# SMT_sheet.net
KiCad netlist of a schematic drawn in Altium Designer
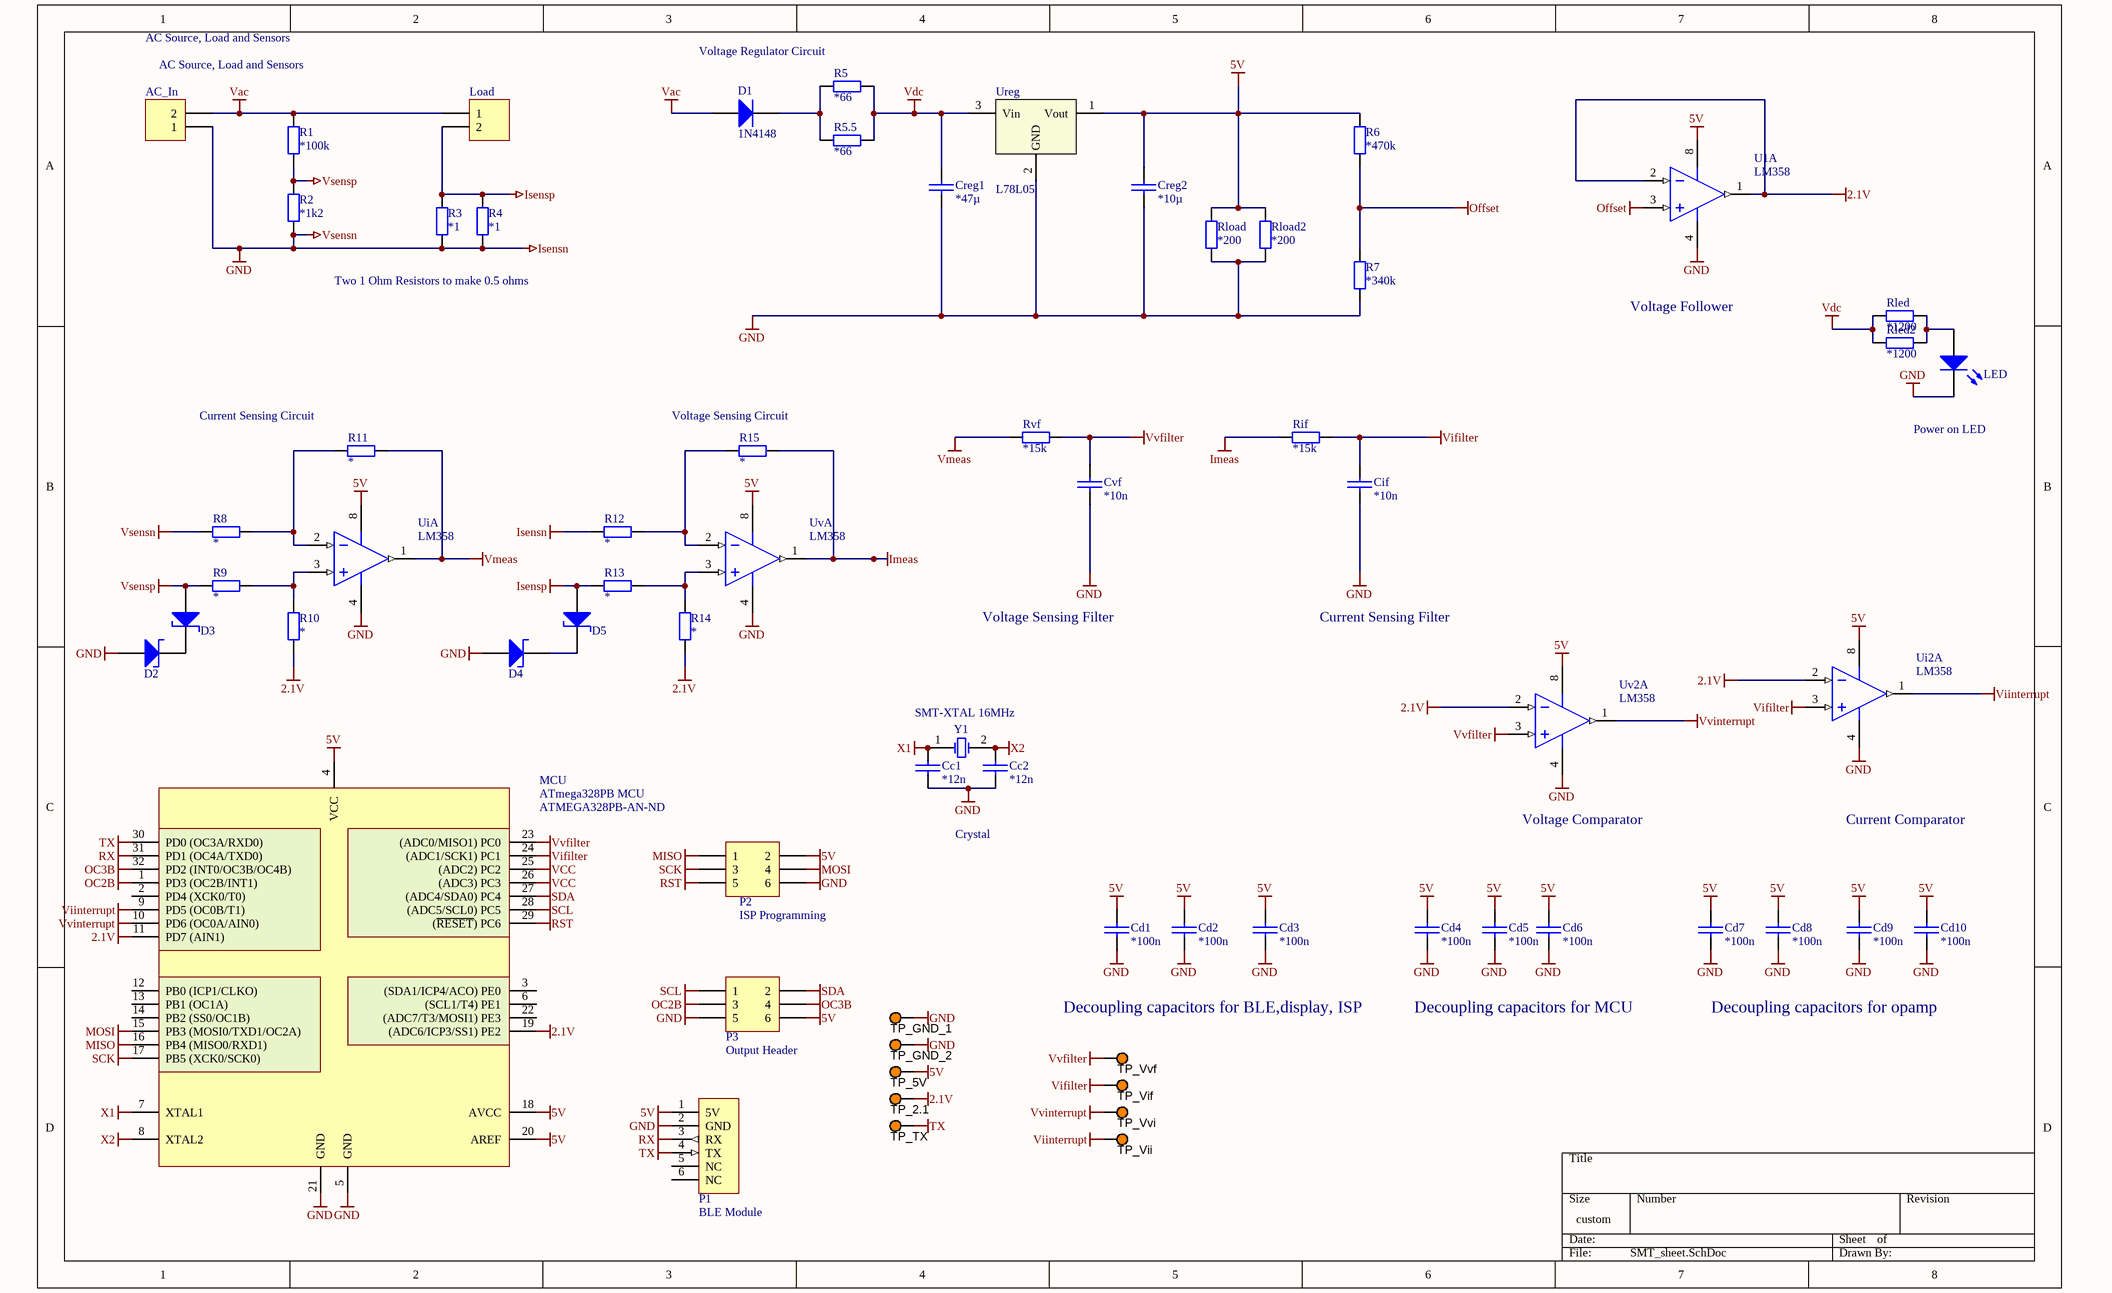
[diagram p0: SMT_sheet.SchDoc]

(export (version "E")
  (design (tool "Eeschema 10.0.6"))
  (components
    (comp (ref "AC_In")
      (value "Header 2")
      (footprint "ece-HDR1X2")
      (description "Header, 2-Pin")
      (fields (field (name "PUBLISHER") "Altium Limited"))
      (libsource (lib "ece components") (part "Header 2"))
    )
    (comp (ref "Cc1")
      (value "*12n")
      (footprint "0805 CAP")
      (description "SMT ceramic capacitor 0805 size")
      (libsource (lib "EE209_Library") (part "CerCap_SMT_0805"))
    )
    (comp (ref "Cc2")
      (value "*12n")
      (footprint "0805 CAP")
      (description "SMT ceramic capacitor 0805 size")
      (libsource (lib "EE209_Library") (part "CerCap_SMT_0805"))
    )
    (comp (ref "Cd1")
      (value "*100n")
      (footprint "0805 CAP")
      (description "SMT ceramic capacitor 0805 size")
      (libsource (lib "EE209_Library") (part "CerCap_SMT_0805"))
    )
    (comp (ref "Cd2")
      (value "*100n")
      (footprint "0805 CAP")
      (description "SMT ceramic capacitor 0805 size")
      (libsource (lib "EE209_Library") (part "CerCap_SMT_0805"))
    )
    (comp (ref "Cd3")
      (value "*100n")
      (footprint "0805 CAP")
      (description "SMT ceramic capacitor 0805 size")
      (libsource (lib "EE209_Library") (part "CerCap_SMT_0805"))
    )
    (comp (ref "Cd4")
      (value "*100n")
      (footprint "0805 CAP")
      (description "SMT ceramic capacitor 0805 size")
      (libsource (lib "EE209_Library") (part "CerCap_SMT_0805"))
    )
    (comp (ref "Cd5")
      (value "*100n")
      (footprint "0805 CAP")
      (description "SMT ceramic capacitor 0805 size")
      (libsource (lib "EE209_Library") (part "CerCap_SMT_0805"))
    )
    (comp (ref "Cd6")
      (value "*100n")
      (footprint "0805 CAP")
      (description "SMT ceramic capacitor 0805 size")
      (libsource (lib "EE209_Library") (part "CerCap_SMT_0805"))
    )
    (comp (ref "Cd7")
      (value "*100n")
      (footprint "0805 CAP")
      (description "SMT ceramic capacitor 0805 size")
      (libsource (lib "EE209_Library") (part "CerCap_SMT_0805"))
    )
    (comp (ref "Cd8")
      (value "*100n")
      (footprint "0805 CAP")
      (description "SMT ceramic capacitor 0805 size")
      (libsource (lib "EE209_Library") (part "CerCap_SMT_0805"))
    )
    (comp (ref "Cd9")
      (value "*100n")
      (footprint "0805 CAP")
      (description "SMT ceramic capacitor 0805 size")
      (libsource (lib "EE209_Library") (part "CerCap_SMT_0805"))
    )
    (comp (ref "Cd10")
      (value "*100n")
      (footprint "0805 CAP")
      (description "SMT ceramic capacitor 0805 size")
      (libsource (lib "EE209_Library") (part "CerCap_SMT_0805"))
    )
    (comp (ref "Cif")
      (value "*10n")
      (footprint "0805 CAP")
      (description "SMT ceramic capacitor 0805 size")
      (libsource (lib "EE209_Library") (part "CerCap_SMT_0805"))
    )
    (comp (ref "Creg1")
      (value "*47µ")
      (footprint "0805 CAP")
      (description "SMT ceramic capacitor 0805 size")
      (libsource (lib "EE209_Library") (part "CerCap_SMT_0805"))
    )
    (comp (ref "Creg2")
      (value "*10µ")
      (footprint "0805 CAP")
      (description "SMT ceramic capacitor 0805 size")
      (libsource (lib "EE209_Library") (part "CerCap_SMT_0805"))
    )
    (comp (ref "Cvf")
      (value "*10n")
      (footprint "0805 CAP")
      (description "SMT ceramic capacitor 0805 size")
      (libsource (lib "EE209_Library") (part "CerCap_SMT_0805"))
    )
    (comp (ref "D1")
      (value "1N4148")
      (footprint "DO214-MFG")
      (description "1N4148 100V 200mA SOD-123 diode")
      (fields
        (field (name "MANUFACTURER") "ON Semiconductor")
        (field (name "MANUFACTURER PART NUMBER") "1N4148TR")
      )
      (libsource (lib "EE209_Library") (part "ES1H_SMT_DO214"))
    )
    (comp (ref "D2")
      (value "BZT52H-B4V7")
      (footprint "SOD123")
      (description "SMT zener diode with SOD123 package")
      (fields
        (field (name "MANUFACTURER") "Nexperia USA Inc.")
        (field (name "MANUFACTURER PART NUMBER") "BZT52H-B4V7,115")
      )
      (libsource (lib "EE209_Library") (part "Zener_SMT_SOD123"))
    )
    (comp (ref "D3")
      (value "BZT52H-B4V7")
      (footprint "SOD123")
      (description "SMT zener diode with SOD123 package")
      (fields
        (field (name "MANUFACTURER") "Nexperia USA Inc.")
        (field (name "MANUFACTURER PART NUMBER") "BZT52H-B4V7,115")
      )
      (libsource (lib "EE209_Library") (part "Zener_SMT_SOD123"))
    )
    (comp (ref "D4")
      (value "BZT52H-B4V7")
      (footprint "SOD123")
      (description "SMT zener diode with SOD123 package")
      (fields
        (field (name "MANUFACTURER") "Nexperia USA Inc.")
        (field (name "MANUFACTURER PART NUMBER") "BZT52H-B4V7,115")
      )
      (libsource (lib "EE209_Library") (part "Zener_SMT_SOD123"))
    )
    (comp (ref "D5")
      (value "BZT52H-B4V7")
      (footprint "SOD123")
      (description "SMT zener diode with SOD123 package")
      (fields
        (field (name "MANUFACTURER") "Nexperia USA Inc.")
        (field (name "MANUFACTURER PART NUMBER") "BZT52H-B4V7,115")
      )
      (libsource (lib "EE209_Library") (part "Zener_SMT_SOD123"))
    )
    (comp (ref "LED")
      (value "LTST-C170KGKT")
      (footprint "0805 LED")
      (description "SMT LED 0805 size")
      (fields (field (name "MANUFACTURER") "Lite-On Inc."))
      (libsource (lib "EE209_Library") (part "LED_SMT_0805"))
    )
    (comp (ref "Load")
      (value "Header 2")
      (footprint "ece-HDR1X2")
      (description "Header, 2-Pin")
      (fields (field (name "PUBLISHER") "Altium Limited"))
      (libsource (lib "") (part "Header 2_1"))
    )
    (comp (ref "MCU")
      (value "ATmega328PB MCU")
      (footprint "32 - TQFP")
      (description "IC MCU 8BIT 32KB FLASH 32TQFP")
      (fields
        (field (name "MANUFACTURER") "Atmel")
        (field (name "MANUFACTURER PART NUMBER") "ATMEGA328PB-AN")
        (field (name "SUPPLIER PART NUMBER 1") "ATMEGA328PB-AN-ND")
      )
      (libsource (lib "EE209_Library") (part "ATmega328PB_SMT_TQFP32"))
    )
    (comp (ref "P1")
      (value "BLE Module Header")
      (footprint "HM10_HDR1X6")
      (description "2.54mm pitch 6-pin header for BLE module")
      (fields (field (name "PUBLISHER") "Altium Limited"))
      (libsource (lib "EE209_Library") (part "BLEModule_TH"))
    )
    (comp (ref "P2")
      (value "Header 3X2")
      (footprint "ECE-BHDR2X3")
      (libsource (lib "ece components") (part "Header 3X2"))
    )
    (comp (ref "P3")
      (value "Header 3X2")
      (footprint "ECE-BHDR2X3")
      (libsource (lib "ece components") (part "Header 3X2"))
    )
    (comp (ref "R1")
      (value "*100k")
      (footprint "0805 RES")
      (description "0805 resistor")
      (fields (field (name "PUBLISHER") "Altium Limited"))
      (libsource (lib "") (part "Res_SMT_0805_1"))
    )
    (comp (ref "R2")
      (value "*1k2")
      (footprint "0805 RES")
      (description "0805 resistor")
      (fields (field (name "PUBLISHER") "Altium Limited"))
      (libsource (lib "") (part "Res_SMT_0805_1"))
    )
    (comp (ref "R3")
      (value "*1")
      (footprint "0805 RES")
      (description "0805 resistor")
      (fields (field (name "PUBLISHER") "Altium Limited"))
      (libsource (lib "") (part "Res_SMT_0805_1"))
    )
    (comp (ref "R4")
      (value "*1")
      (footprint "0805 RES")
      (description "0805 resistor")
      (fields (field (name "PUBLISHER") "Altium Limited"))
      (libsource (lib "") (part "Res_SMT_0805_1"))
    )
    (comp (ref "R5")
      (value "*66")
      (footprint "0805 RES")
      (description "0805 resistor")
      (fields (field (name "PUBLISHER") "Altium Limited"))
      (libsource (lib "EE209_Library") (part "Res_SMT_0805"))
    )
    (comp (ref "R5.5")
      (value "*66")
      (footprint "0805 RES")
      (description "0805 resistor")
      (fields (field (name "PUBLISHER") "Altium Limited"))
      (libsource (lib "EE209_Library") (part "Res_SMT_0805"))
    )
    (comp (ref "R6")
      (value "*470k")
      (footprint "0805 RES")
      (description "0805 resistor")
      (fields (field (name "PUBLISHER") "Altium Limited"))
      (libsource (lib "") (part "Res_SMT_0805_1"))
    )
    (comp (ref "R7")
      (value "*340k")
      (footprint "0805 RES")
      (description "0805 resistor")
      (fields (field (name "PUBLISHER") "Altium Limited"))
      (libsource (lib "") (part "Res_SMT_0805_1"))
    )
    (comp (ref "R8")
      (value "*")
      (footprint "0805 RES")
      (description "0805 resistor")
      (fields (field (name "PUBLISHER") "Altium Limited"))
      (libsource (lib "EE209_Library") (part "Res_SMT_0805"))
    )
    (comp (ref "R9")
      (value "*")
      (footprint "0805 RES")
      (description "0805 resistor")
      (fields (field (name "PUBLISHER") "Altium Limited"))
      (libsource (lib "EE209_Library") (part "Res_SMT_0805"))
    )
    (comp (ref "R10")
      (value "*")
      (footprint "0805 RES")
      (description "0805 resistor")
      (fields (field (name "PUBLISHER") "Altium Limited"))
      (libsource (lib "") (part "Res_SMT_0805_1"))
    )
    (comp (ref "R11")
      (value "*")
      (footprint "0805 RES")
      (description "0805 resistor")
      (fields (field (name "PUBLISHER") "Altium Limited"))
      (libsource (lib "EE209_Library") (part "Res_SMT_0805"))
    )
    (comp (ref "R12")
      (value "*")
      (footprint "0805 RES")
      (description "0805 resistor")
      (fields (field (name "PUBLISHER") "Altium Limited"))
      (libsource (lib "EE209_Library") (part "Res_SMT_0805"))
    )
    (comp (ref "R13")
      (value "*")
      (footprint "0805 RES")
      (description "0805 resistor")
      (fields (field (name "PUBLISHER") "Altium Limited"))
      (libsource (lib "EE209_Library") (part "Res_SMT_0805"))
    )
    (comp (ref "R14")
      (value "*")
      (footprint "0805 RES")
      (description "0805 resistor")
      (fields (field (name "PUBLISHER") "Altium Limited"))
      (libsource (lib "") (part "Res_SMT_0805_1"))
    )
    (comp (ref "R15")
      (value "*")
      (footprint "0805 RES")
      (description "0805 resistor")
      (fields (field (name "PUBLISHER") "Altium Limited"))
      (libsource (lib "EE209_Library") (part "Res_SMT_0805"))
    )
    (comp (ref "Rif")
      (value "*15k")
      (footprint "0805 RES")
      (description "0805 resistor")
      (fields (field (name "PUBLISHER") "Altium Limited"))
      (libsource (lib "EE209_Library") (part "Res_SMT_0805"))
    )
    (comp (ref "Rled")
      (value "*1200")
      (footprint "0805 RES")
      (description "0805 resistor")
      (fields (field (name "PUBLISHER") "Altium Limited"))
      (libsource (lib "EE209_Library") (part "Res_SMT_0805"))
    )
    (comp (ref "Rled2")
      (value "*1200")
      (footprint "0805 RES")
      (description "0805 resistor")
      (fields (field (name "PUBLISHER") "Altium Limited"))
      (libsource (lib "EE209_Library") (part "Res_SMT_0805"))
    )
    (comp (ref "Rload")
      (value "*200")
      (footprint "0805 RES")
      (description "0805 resistor")
      (fields (field (name "PUBLISHER") "Altium Limited"))
      (libsource (lib "") (part "Res_SMT_0805_1"))
    )
    (comp (ref "Rload2")
      (value "*200")
      (footprint "0805 RES")
      (description "0805 resistor")
      (fields (field (name "PUBLISHER") "Altium Limited"))
      (libsource (lib "") (part "Res_SMT_0805_1"))
    )
    (comp (ref "Rvf")
      (value "*15k")
      (footprint "0805 RES")
      (description "0805 resistor")
      (fields (field (name "PUBLISHER") "Altium Limited"))
      (libsource (lib "EE209_Library") (part "Res_SMT_0805"))
    )
    (comp (ref "TP_2.1")
      (value "5003")
      (footprint "TP_TH")
      (description "Test Point, Orange, 1-Pin THD, RoHS")
      (libsource (lib "EE209_Library") (part "TestPoint"))
    )
    (comp (ref "TP_5V")
      (value "5003")
      (footprint "TP_TH")
      (description "Test Point, Orange, 1-Pin THD, RoHS")
      (libsource (lib "EE209_Library") (part "TestPoint"))
    )
    (comp (ref "TP_GND_1")
      (value "5003")
      (footprint "TP_TH")
      (description "Test Point, Orange, 1-Pin THD, RoHS")
      (libsource (lib "EE209_Library") (part "TestPoint"))
    )
    (comp (ref "TP_GND_2")
      (value "5003")
      (footprint "TP_TH")
      (description "Test Point, Orange, 1-Pin THD, RoHS")
      (libsource (lib "EE209_Library") (part "TestPoint"))
    )
    (comp (ref "TP_TX")
      (value "5003")
      (footprint "TP_TH")
      (description "Test Point, Orange, 1-Pin THD, RoHS")
      (libsource (lib "EE209_Library") (part "TestPoint"))
    )
    (comp (ref "TP_Vif")
      (value "5003")
      (footprint "TP_TH")
      (description "Test Point, Orange, 1-Pin THD, RoHS")
      (libsource (lib "EE209_Library") (part "TestPoint"))
    )
    (comp (ref "TP_Vii")
      (value "5003")
      (footprint "TP_TH")
      (description "Test Point, Orange, 1-Pin THD, RoHS")
      (libsource (lib "EE209_Library") (part "TestPoint"))
    )
    (comp (ref "TP_Vvf")
      (value "5003")
      (footprint "TP_TH")
      (description "Test Point, Orange, 1-Pin THD, RoHS")
      (libsource (lib "EE209_Library") (part "TestPoint"))
    )
    (comp (ref "TP_Vvi")
      (value "5003")
      (footprint "TP_TH")
      (description "Test Point, Orange, 1-Pin THD, RoHS")
      (libsource (lib "EE209_Library") (part "TestPoint"))
    )
    (comp (ref "U1")
      (value "LM358")
      (footprint "SO - 8")
      (description "IC OPAMP 8SOIC")
      (libsource (lib "EE209_Library") (part "LM358_SMT_SOIC8"))
    )
    (comp (ref "Ui")
      (value "LM358")
      (footprint "SO - 8")
      (description "IC OPAMP 8SOIC")
      (libsource (lib "EE209_Library") (part "LM358_SMT_SOIC8"))
    )
    (comp (ref "Ui2")
      (value "LM358")
      (footprint "SO - 8")
      (description "IC OPAMP 8SOIC")
      (libsource (lib "EE209_Library") (part "LM358_SMT_SOIC8"))
    )
    (comp (ref "Ureg")
      (value "L78L05")
      (footprint "SOT-89")
      (description "LDO Voltage Regulator 5V")
      (libsource (lib "EE209_Library") (part "L78L05_SMT_SOT89"))
    )
    (comp (ref "Uv")
      (value "LM358")
      (footprint "SO - 8")
      (description "IC OPAMP 8SOIC")
      (libsource (lib "EE209_Library") (part "LM358_SMT_SOIC8"))
    )
    (comp (ref "Uv2")
      (value "LM358")
      (footprint "SO - 8")
      (description "IC OPAMP 8SOIC")
      (libsource (lib "EE209_Library") (part "LM358_SMT_SOIC8"))
    )
    (comp (ref "Y1")
      (value "SMT-XTAL 16MHz")
      (footprint "HC49-US")
      (description "9C-16.000MAAJ-T crystal 16.0000MHZ 18PF SMD")
      (fields
        (field (name "MANUFACTURER") "TXC CORPORATION")
        (field (name "MANUFACTURER PART NUMBER") "9C-16.000MAAJ-T")
      )
      (libsource (lib "EE209_Library") (part "TXC9C-16_XTAL_SMT"))
    )
  )
  (nets
    (net (code "1") (name "2.1V") (class "Default")
      (node (ref "MCU") (pin "11") (pinfunction "PD7_(AIN1)_11") (pintype "passive"))
      (node (ref "MCU") (pin "19") (pinfunction "(ADC6/ICP3/SS1)_PE2_19") (pintype "passive"))
      (node (ref "R10") (pin "1") (pinfunction "1_1") (pintype "passive"))
      (node (ref "R14") (pin "1") (pinfunction "1_1") (pintype "passive"))
      (node (ref "TP_2.1") (pin "1") (pinfunction "1_1") (pintype "passive"))
      (node (ref "U1") (pin "1") (pinfunction "VOUTA_1") (pintype "output"))
      (node (ref "U1") (pin "2") (pinfunction "VINA-_2") (pintype "input"))
      (node (ref "Ui2") (pin "2") (pinfunction "VINA-_2") (pintype "input"))
      (node (ref "Uv2") (pin "2") (pinfunction "VINA-_2") (pintype "input"))
    )
    (net (code "2") (name "5V") (class "Default")
      (node (ref "Cd1") (pin "1") (pinfunction "1_1") (pintype "passive"))
      (node (ref "Cd10") (pin "1") (pinfunction "1_1") (pintype "passive"))
      (node (ref "Cd2") (pin "1") (pinfunction "1_1") (pintype "passive"))
      (node (ref "Cd3") (pin "1") (pinfunction "1_1") (pintype "passive"))
      (node (ref "Cd4") (pin "1") (pinfunction "1_1") (pintype "passive"))
      (node (ref "Cd5") (pin "1") (pinfunction "1_1") (pintype "passive"))
      (node (ref "Cd6") (pin "1") (pinfunction "1_1") (pintype "passive"))
      (node (ref "Cd7") (pin "1") (pinfunction "1_1") (pintype "passive"))
      (node (ref "Cd8") (pin "1") (pinfunction "1_1") (pintype "passive"))
      (node (ref "Cd9") (pin "1") (pinfunction "1_1") (pintype "passive"))
      (node (ref "Creg2") (pin "1") (pinfunction "1_1") (pintype "passive"))
      (node (ref "MCU") (pin "18") (pinfunction "AVCC_18") (pintype "passive"))
      (node (ref "MCU") (pin "20") (pinfunction "AREF_20") (pintype "passive"))
      (node (ref "MCU") (pin "4") (pinfunction "VCC_4") (pintype "passive"))
      (node (ref "P1") (pin "1") (pinfunction "5V_1") (pintype "passive"))
      (node (ref "P2") (pin "2") (pinfunction "2_2") (pintype "passive"))
      (node (ref "P3") (pin "6") (pinfunction "6_6") (pintype "passive"))
      (node (ref "R6") (pin "2") (pinfunction "2_2") (pintype "passive"))
      (node (ref "Rload") (pin "2") (pinfunction "2_2") (pintype "passive"))
      (node (ref "Rload2") (pin "2") (pinfunction "2_2") (pintype "passive"))
      (node (ref "TP_5V") (pin "1") (pinfunction "1_1") (pintype "passive"))
      (node (ref "U1") (pin "8") (pinfunction "VDD_8") (pintype "power_in"))
      (node (ref "Ui") (pin "8") (pinfunction "VDD_8") (pintype "power_in"))
      (node (ref "Ui2") (pin "8") (pinfunction "VDD_8") (pintype "power_in"))
      (node (ref "Ureg") (pin "1") (pinfunction "Vout_1") (pintype "passive"))
      (node (ref "Uv") (pin "8") (pinfunction "VDD_8") (pintype "power_in"))
      (node (ref "Uv2") (pin "8") (pinfunction "VDD_8") (pintype "power_in"))
    )
    (net (code "3") (name "GND") (class "Default")
      (node (ref "AC_In") (pin "1") (pinfunction "1_1") (pintype "passive"))
      (node (ref "Cc1") (pin "2") (pinfunction "2_2") (pintype "passive"))
      (node (ref "Cc2") (pin "2") (pinfunction "2_2") (pintype "passive"))
      (node (ref "Cd1") (pin "2") (pinfunction "2_2") (pintype "passive"))
      (node (ref "Cd10") (pin "2") (pinfunction "2_2") (pintype "passive"))
      (node (ref "Cd2") (pin "2") (pinfunction "2_2") (pintype "passive"))
      (node (ref "Cd3") (pin "2") (pinfunction "2_2") (pintype "passive"))
      (node (ref "Cd4") (pin "2") (pinfunction "2_2") (pintype "passive"))
      (node (ref "Cd5") (pin "2") (pinfunction "2_2") (pintype "passive"))
      (node (ref "Cd6") (pin "2") (pinfunction "2_2") (pintype "passive"))
      (node (ref "Cd7") (pin "2") (pinfunction "2_2") (pintype "passive"))
      (node (ref "Cd8") (pin "2") (pinfunction "2_2") (pintype "passive"))
      (node (ref "Cd9") (pin "2") (pinfunction "2_2") (pintype "passive"))
      (node (ref "Cif") (pin "2") (pinfunction "2_2") (pintype "passive"))
      (node (ref "Creg1") (pin "2") (pinfunction "2_2") (pintype "passive"))
      (node (ref "Creg2") (pin "2") (pinfunction "2_2") (pintype "passive"))
      (node (ref "Cvf") (pin "2") (pinfunction "2_2") (pintype "passive"))
      (node (ref "D2") (pin "1") (pinfunction "A_1") (pintype "passive"))
      (node (ref "D4") (pin "1") (pinfunction "A_1") (pintype "passive"))
      (node (ref "LED") (pin "2") (pinfunction "K_2") (pintype "passive"))
      (node (ref "MCU") (pin "21") (pinfunction "GND_21") (pintype "passive"))
      (node (ref "MCU") (pin "5") (pinfunction "GND_5") (pintype "passive"))
      (node (ref "P1") (pin "2") (pinfunction "GND_2") (pintype "passive"))
      (node (ref "P2") (pin "6") (pinfunction "6_6") (pintype "passive"))
      (node (ref "P3") (pin "5") (pinfunction "5_5") (pintype "passive"))
      (node (ref "R12") (pin "1") (pinfunction "1_1") (pintype "passive"))
      (node (ref "R2") (pin "1") (pinfunction "1_1") (pintype "passive"))
      (node (ref "R3") (pin "1") (pinfunction "1_1") (pintype "passive"))
      (node (ref "R4") (pin "1") (pinfunction "1_1") (pintype "passive"))
      (node (ref "R7") (pin "1") (pinfunction "1_1") (pintype "passive"))
      (node (ref "R8") (pin "1") (pinfunction "1_1") (pintype "passive"))
      (node (ref "Rload") (pin "1") (pinfunction "1_1") (pintype "passive"))
      (node (ref "Rload2") (pin "1") (pinfunction "1_1") (pintype "passive"))
      (node (ref "TP_GND_1") (pin "1") (pinfunction "1_1") (pintype "passive"))
      (node (ref "TP_GND_2") (pin "1") (pinfunction "1_1") (pintype "passive"))
      (node (ref "U1") (pin "4") (pinfunction "VSS_4") (pintype "power_in"))
      (node (ref "Ui") (pin "4") (pinfunction "VSS_4") (pintype "power_in"))
      (node (ref "Ui2") (pin "4") (pinfunction "VSS_4") (pintype "power_in"))
      (node (ref "Ureg") (pin "2") (pinfunction "GND_2") (pintype "passive"))
      (node (ref "Uv") (pin "4") (pinfunction "VSS_4") (pintype "power_in"))
      (node (ref "Uv2") (pin "4") (pinfunction "VSS_4") (pintype "power_in"))
    )
    (net (code "4") (name "Imeas") (class "Default")
      (node (ref "R15") (pin "2") (pinfunction "2_2") (pintype "passive"))
      (node (ref "Rif") (pin "1") (pinfunction "1_1") (pintype "passive"))
      (node (ref "Uv") (pin "1") (pinfunction "VOUTA_1") (pintype "output"))
    )
    (net (code "5") (name "Isensp") (class "Default")
      (node (ref "D5") (pin "1") (pinfunction "A_1") (pintype "passive"))
      (node (ref "Load") (pin "2") (pinfunction "2_2") (pintype "passive"))
      (node (ref "R13") (pin "1") (pinfunction "1_1") (pintype "passive"))
      (node (ref "R3") (pin "2") (pinfunction "2_2") (pintype "passive"))
      (node (ref "R4") (pin "2") (pinfunction "2_2") (pintype "passive"))
    )
    (net (code "6") (name "MISO") (class "Default")
      (node (ref "MCU") (pin "16") (pinfunction "PB4_(MISO0/RXD1)_16") (pintype "passive"))
      (node (ref "P2") (pin "1") (pinfunction "1_1") (pintype "passive"))
    )
    (net (code "7") (name "MOSI") (class "Default")
      (node (ref "MCU") (pin "15") (pinfunction "PB3_(MOSI0/TXD1/OC2A)_15") (pintype "passive"))
      (node (ref "P2") (pin "4") (pinfunction "4_4") (pintype "passive"))
    )
    (net (code "8") (name "Net-(D1-K)") (class "Default")
      (node (ref "D1") (pin "2") (pinfunction "K_2") (pintype "passive"))
      (node (ref "R5") (pin "1") (pinfunction "1_1") (pintype "passive"))
      (node (ref "R5.5") (pin "1") (pinfunction "1_1") (pintype "passive"))
    )
    (net (code "9") (name "Net-(D2-K)") (class "Default")
      (node (ref "D2") (pin "2") (pinfunction "K_2") (pintype "passive"))
      (node (ref "D3") (pin "2") (pinfunction "K_2") (pintype "passive"))
    )
    (net (code "10") (name "Net-(D4-K)") (class "Default")
      (node (ref "D4") (pin "2") (pinfunction "K_2") (pintype "passive"))
      (node (ref "D5") (pin "2") (pinfunction "K_2") (pintype "passive"))
    )
    (net (code "11") (name "Net-(LED-A)") (class "Default")
      (node (ref "LED") (pin "1") (pinfunction "A_1") (pintype "passive"))
      (node (ref "Rled") (pin "2") (pinfunction "2_2") (pintype "passive"))
      (node (ref "Rled2") (pin "2") (pinfunction "2_2") (pintype "passive"))
    )
    (net (code "12") (name "Net-(UiA-VINA+)") (class "Default")
      (node (ref "R10") (pin "2") (pinfunction "2_2") (pintype "passive"))
      (node (ref "R9") (pin "2") (pinfunction "2_2") (pintype "passive"))
      (node (ref "Ui") (pin "3") (pinfunction "VINA+_3") (pintype "input"))
    )
    (net (code "13") (name "Net-(UiA-VINA-)") (class "Default")
      (node (ref "R11") (pin "1") (pinfunction "1_1") (pintype "passive"))
      (node (ref "R8") (pin "2") (pinfunction "2_2") (pintype "passive"))
      (node (ref "Ui") (pin "2") (pinfunction "VINA-_2") (pintype "input"))
    )
    (net (code "14") (name "Net-(UvA-VINA+)") (class "Default")
      (node (ref "R13") (pin "2") (pinfunction "2_2") (pintype "passive"))
      (node (ref "R14") (pin "2") (pinfunction "2_2") (pintype "passive"))
      (node (ref "Uv") (pin "3") (pinfunction "VINA+_3") (pintype "input"))
    )
    (net (code "15") (name "Net-(UvA-VINA-)") (class "Default")
      (node (ref "R12") (pin "2") (pinfunction "2_2") (pintype "passive"))
      (node (ref "R15") (pin "1") (pinfunction "1_1") (pintype "passive"))
      (node (ref "Uv") (pin "2") (pinfunction "VINA-_2") (pintype "input"))
    )
    (net (code "16") (name "OC2B") (class "Default")
      (node (ref "MCU") (pin "1") (pinfunction "PD3_(OC2B/INT1)_1") (pintype "passive"))
      (node (ref "P3") (pin "3") (pinfunction "3_3") (pintype "passive"))
    )
    (net (code "17") (name "OC3B") (class "Default")
      (node (ref "MCU") (pin "32") (pinfunction "PD2_(INT0/OC3B/OC4B)_32") (pintype "passive"))
      (node (ref "P3") (pin "4") (pinfunction "4_4") (pintype "passive"))
    )
    (net (code "18") (name "Offset") (class "Default")
      (node (ref "R6") (pin "1") (pinfunction "1_1") (pintype "passive"))
      (node (ref "R7") (pin "2") (pinfunction "2_2") (pintype "passive"))
      (node (ref "U1") (pin "3") (pinfunction "VINA+_3") (pintype "input"))
    )
    (net (code "19") (name "RST") (class "Default")
      (node (ref "MCU") (pin "29") (pinfunction "(~{RESET})_PC6_29") (pintype "passive"))
      (node (ref "P2") (pin "5") (pinfunction "5_5") (pintype "passive"))
    )
    (net (code "20") (name "RX") (class "Default")
      (node (ref "MCU") (pin "31") (pinfunction "PD1_(OC4A/TXD0)_31") (pintype "passive"))
      (node (ref "P1") (pin "3") (pinfunction "RX_3") (pintype "output"))
    )
    (net (code "21") (name "SCK") (class "Default")
      (node (ref "MCU") (pin "17") (pinfunction "PB5_(XCK0/SCK0)_17") (pintype "passive"))
      (node (ref "P2") (pin "3") (pinfunction "3_3") (pintype "passive"))
    )
    (net (code "22") (name "SCL") (class "Default")
      (node (ref "MCU") (pin "28") (pinfunction "(ADC5/SCL0)_PC5_28") (pintype "passive"))
      (node (ref "P3") (pin "1") (pinfunction "1_1") (pintype "passive"))
    )
    (net (code "23") (name "SDA") (class "Default")
      (node (ref "MCU") (pin "27") (pinfunction "(ADC4/SDA0)_PC4_27") (pintype "passive"))
      (node (ref "P3") (pin "2") (pinfunction "2_2") (pintype "passive"))
    )
    (net (code "24") (name "TX") (class "Default")
      (node (ref "MCU") (pin "30") (pinfunction "PD0_(OC3A/RXD0)_30") (pintype "passive"))
      (node (ref "P1") (pin "4") (pinfunction "TX_4") (pintype "input"))
      (node (ref "TP_TX") (pin "1") (pinfunction "1_1") (pintype "passive"))
    )
    (net (code "25") (name "VCC") (class "Default")
      (node (ref "MCU") (pin "25") (pinfunction "(ADC2)_PC2_25") (pintype "passive"))
      (node (ref "MCU") (pin "26") (pinfunction "(ADC3)_PC3_26") (pintype "passive"))
    )
    (net (code "26") (name "Vac") (class "Default")
      (node (ref "AC_In") (pin "2") (pinfunction "2_2") (pintype "passive"))
      (node (ref "D1") (pin "1") (pinfunction "A_1") (pintype "passive"))
      (node (ref "Load") (pin "1") (pinfunction "1_1") (pintype "passive"))
      (node (ref "R1") (pin "2") (pinfunction "2_2") (pintype "passive"))
    )
    (net (code "27") (name "Vdc") (class "Default")
      (node (ref "Creg1") (pin "1") (pinfunction "1_1") (pintype "passive"))
      (node (ref "R5") (pin "2") (pinfunction "2_2") (pintype "passive"))
      (node (ref "R5.5") (pin "2") (pinfunction "2_2") (pintype "passive"))
      (node (ref "Rled") (pin "1") (pinfunction "1_1") (pintype "passive"))
      (node (ref "Rled2") (pin "1") (pinfunction "1_1") (pintype "passive"))
      (node (ref "Ureg") (pin "3") (pinfunction "Vin_3") (pintype "passive"))
    )
    (net (code "28") (name "Vifilter") (class "Default")
      (node (ref "Cif") (pin "1") (pinfunction "1_1") (pintype "passive"))
      (node (ref "MCU") (pin "24") (pinfunction "(ADC1/SCK1)_PC1_24") (pintype "passive"))
      (node (ref "Rif") (pin "2") (pinfunction "2_2") (pintype "passive"))
      (node (ref "TP_Vif") (pin "1") (pinfunction "1_1") (pintype "passive"))
      (node (ref "Ui2") (pin "3") (pinfunction "VINA+_3") (pintype "input"))
    )
    (net (code "29") (name "Viinterrupt") (class "Default")
      (node (ref "MCU") (pin "9") (pinfunction "PD5_(OC0B/T1)_9") (pintype "passive"))
      (node (ref "TP_Vii") (pin "1") (pinfunction "1_1") (pintype "passive"))
      (node (ref "Ui2") (pin "1") (pinfunction "VOUTA_1") (pintype "output"))
    )
    (net (code "30") (name "Vmeas") (class "Default")
      (node (ref "R11") (pin "2") (pinfunction "2_2") (pintype "passive"))
      (node (ref "Rvf") (pin "1") (pinfunction "1_1") (pintype "passive"))
      (node (ref "Ui") (pin "1") (pinfunction "VOUTA_1") (pintype "output"))
    )
    (net (code "31") (name "Vsensp") (class "Default")
      (node (ref "D3") (pin "1") (pinfunction "A_1") (pintype "passive"))
      (node (ref "R1") (pin "1") (pinfunction "1_1") (pintype "passive"))
      (node (ref "R2") (pin "2") (pinfunction "2_2") (pintype "passive"))
      (node (ref "R9") (pin "1") (pinfunction "1_1") (pintype "passive"))
    )
    (net (code "32") (name "Vvfilter") (class "Default")
      (node (ref "Cvf") (pin "1") (pinfunction "1_1") (pintype "passive"))
      (node (ref "MCU") (pin "23") (pinfunction "(ADC0/MISO1)_PC0_23") (pintype "passive"))
      (node (ref "Rvf") (pin "2") (pinfunction "2_2") (pintype "passive"))
      (node (ref "TP_Vvf") (pin "1") (pinfunction "1_1") (pintype "passive"))
      (node (ref "Uv2") (pin "3") (pinfunction "VINA+_3") (pintype "input"))
    )
    (net (code "33") (name "Vvinterrupt") (class "Default")
      (node (ref "MCU") (pin "10") (pinfunction "PD6_(OC0A/AIN0)_10") (pintype "passive"))
      (node (ref "TP_Vvi") (pin "1") (pinfunction "1_1") (pintype "passive"))
      (node (ref "Uv2") (pin "1") (pinfunction "VOUTA_1") (pintype "output"))
    )
    (net (code "34") (name "X1") (class "Default")
      (node (ref "Cc1") (pin "1") (pinfunction "1_1") (pintype "passive"))
      (node (ref "MCU") (pin "7") (pinfunction "XTAL1_7") (pintype "passive"))
      (node (ref "Y1") (pin "1") (pinfunction "OSC1_1") (pintype "passive"))
    )
    (net (code "35") (name "X2") (class "Default")
      (node (ref "Cc2") (pin "1") (pinfunction "1_1") (pintype "passive"))
      (node (ref "MCU") (pin "8") (pinfunction "XTAL2_8") (pintype "passive"))
      (node (ref "Y1") (pin "2") (pinfunction "OSC2_2") (pintype "passive"))
    )
    (net (code "36") (name "unconnected-(MCU-(ADC7{slash}T3{slash}MOSI1)_PE3-Pad22)") (class "Default")
      (node (ref "MCU") (pin "22") (pinfunction "(ADC7/T3/MOSI1)_PE3_22") (pintype "passive"))
    )
    (net (code "37") (name "unconnected-(MCU-(SCL1{slash}T4)_PE1-Pad6)") (class "Default")
      (node (ref "MCU") (pin "6") (pinfunction "(SCL1/T4)_PE1_6") (pintype "passive"))
    )
    (net (code "38") (name "unconnected-(MCU-(SDA1{slash}ICP4{slash}ACO)_PE0-Pad3)") (class "Default")
      (node (ref "MCU") (pin "3") (pinfunction "(SDA1/ICP4/ACO)_PE0_3") (pintype "passive"))
    )
    (net (code "39") (name "unconnected-(MCU-PB0_(ICP1{slash}CLKO)-Pad12)") (class "Default")
      (node (ref "MCU") (pin "12") (pinfunction "PB0_(ICP1/CLKO)_12") (pintype "passive"))
    )
    (net (code "40") (name "unconnected-(MCU-PB1_(OC1A)-Pad13)") (class "Default")
      (node (ref "MCU") (pin "13") (pinfunction "PB1_(OC1A)_13") (pintype "passive"))
    )
    (net (code "41") (name "unconnected-(MCU-PB2_(SS0{slash}OC1B)-Pad14)") (class "Default")
      (node (ref "MCU") (pin "14") (pinfunction "PB2_(SS0/OC1B)_14") (pintype "passive"))
    )
    (net (code "42") (name "unconnected-(MCU-PD4_(XCK0{slash}T0)-Pad2)") (class "Default")
      (node (ref "MCU") (pin "2") (pinfunction "PD4_(XCK0/T0)_2") (pintype "passive"))
    )
    (net (code "43") (name "unconnected-(P1-NC-Pad5)") (class "Default")
      (node (ref "P1") (pin "5") (pinfunction "NC_5") (pintype "passive"))
    )
    (net (code "44") (name "unconnected-(P1-NC-Pad6)") (class "Default")
      (node (ref "P1") (pin "6") (pinfunction "NC_6") (pintype "passive"))
    )
  )
)
